# dcdc.net
KiCad netlist of a schematic drawn in Altium Designer
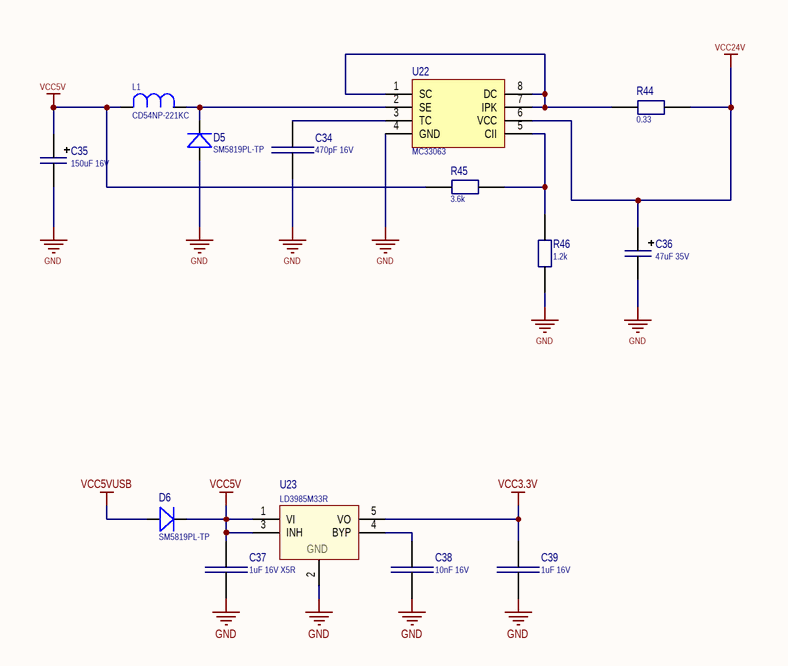
[diagram p0: dcdc.schdoc]

(export (version "E")
  (design (tool "Eeschema 10.0.6"))
  (components
    (comp (ref "C34")
      (value "470pF 16V")
      (footprint "C_0603")
      (description "Capacitor")
      (fields (field (name "PART NUMBER") "CC0603KRX7R9BB471"))
      (libsource (lib "AX_Altium_v2.3") (part "C0603"))
    )
    (comp (ref "C35")
      (value "150uF 16V")
      (footprint "TANTAL_TYPE_D")
      (description "Tantal Capacitor")
      (fields (field (name "PART NUMBER") "T491D157K016AT"))
      (libsource (lib "capacitors") (part "TANTAL_CAP"))
    )
    (comp (ref "C36")
      (value "47uF 35V")
      (footprint "TANTAL_TYPE_X")
      (description "Tantal Capacitor")
      (fields (field (name "PART NUMBER") "T491X476K035AT"))
      (libsource (lib "capacitors") (part "TANTAL_CAP"))
    )
    (comp (ref "C37")
      (value "1uF 16V X5R")
      (footprint "C_0603")
      (description "Capacitor")
      (fields (field (name "PART NUMBER") "CC0603KRX7R7BB105"))
      (libsource (lib "AX_Altium_v2.3") (part "C0603"))
    )
    (comp (ref "C38")
      (value "10nF 16V")
      (footprint "C_0603")
      (description "Capacitor")
      (fields (field (name "PART NUMBER") "CC0603JRX7R7BB103"))
      (libsource (lib "AX_Altium_v2.3") (part "C0603"))
    )
    (comp (ref "C39")
      (value "1uF 16V")
      (footprint "C_0603")
      (description "Capacitor")
      (fields (field (name "PART NUMBER") "CC0603KRX7R7BB105"))
      (libsource (lib "AX_Altium_v2.3") (part "C0603"))
    )
    (comp (ref "D5")
      (value "SM5819PL-TP")
      (footprint "SOD-123")
      (description "Diode")
      (libsource (lib "AX_Altium_v2.3") (part "D_SOD123"))
    )
    (comp (ref "D6")
      (value "SM5819PL-TP")
      (footprint "SOD-123")
      (description "Diode")
      (libsource (lib "AX_Altium_v2.3") (part "D_SOD123"))
    )
    (comp (ref "L1")
      (value "CD54NP-221KC")
      (footprint "CD54NP")
      (description "Inductor")
      (libsource (lib "AX_Altium_v2.3") (part "L_CD54NP"))
    )
    (comp (ref "R44")
      (value "0.33")
      (footprint "R_1206")
      (description "Resistor")
      (fields (field (name "PART NUMBER") "RL1206FR-070R33L"))
      (libsource (lib "resistors") (part "RES_SMD"))
    )
    (comp (ref "R45")
      (value "3.6k")
      (footprint "R_0603")
      (description "Resistor")
      (fields (field (name "PART NUMBER") "RC0603FR-073K6L"))
      (libsource (lib "resistors") (part "RES_SMD"))
    )
    (comp (ref "R46")
      (value "1.2k")
      (footprint "R_0603")
      (description "Resistor")
      (fields (field (name "PART NUMBER") "RC0603FR-071K2L"))
      (libsource (lib "resistors") (part "RES_SMD"))
    )
    (comp (ref "U22")
      (value "MC33063")
      (footprint "SO-8")
      (description "Step-up/down IC")
      (libsource (lib "dcdc_ldo_ref") (part "MC33063"))
    )
    (comp (ref "U23")
      (value "LD3985M33R")
      (footprint "SOT23-5")
      (libsource (lib "AX_Altium_v2.3") (part "LD3985M33R"))
    )
  )
  (nets
    (net (code "1") (name "GND") (class "Default")
      (node (ref "C34") (pin "1") (pinfunction "1_1") (pintype "passive"))
      (node (ref "C35") (pin "2") (pinfunction "2_2") (pintype "passive"))
      (node (ref "C36") (pin "2") (pinfunction "2_2") (pintype "passive"))
      (node (ref "C37") (pin "1") (pinfunction "1_1") (pintype "passive"))
      (node (ref "C38") (pin "1") (pinfunction "1_1") (pintype "passive"))
      (node (ref "C39") (pin "1") (pinfunction "1_1") (pintype "passive"))
      (node (ref "D5") (pin "1") (pinfunction "A_1") (pintype "passive"))
      (node (ref "R46") (pin "1") (pinfunction "1_1") (pintype "passive"))
      (node (ref "U22") (pin "4") (pinfunction "GND_4") (pintype "passive"))
      (node (ref "U23") (pin "2") (pinfunction "GND_2") (pintype "passive"))
    )
    (net (code "2") (name "Net-(D5-K)") (class "Default")
      (node (ref "D5") (pin "2") (pinfunction "K_2") (pintype "passive"))
      (node (ref "L1") (pin "1") (pintype "passive"))
      (node (ref "U22") (pin "2") (pinfunction "SE_2") (pintype "passive"))
    )
    (net (code "3") (name "Net-(U22-CII)") (class "Default")
      (node (ref "R45") (pin "2") (pinfunction "2_2") (pintype "passive"))
      (node (ref "R46") (pin "2") (pinfunction "2_2") (pintype "passive"))
      (node (ref "U22") (pin "5") (pinfunction "CII_5") (pintype "passive"))
    )
    (net (code "4") (name "Net-(U22-DC)") (class "Default")
      (node (ref "R44") (pin "2") (pinfunction "2_2") (pintype "passive"))
      (node (ref "U22") (pin "1") (pinfunction "SC_1") (pintype "passive"))
      (node (ref "U22") (pin "7") (pinfunction "IPK_7") (pintype "passive"))
      (node (ref "U22") (pin "8") (pinfunction "DC_8") (pintype "passive"))
    )
    (net (code "5") (name "Net-(U22-TC)") (class "Default")
      (node (ref "C34") (pin "2") (pinfunction "2_2") (pintype "passive"))
      (node (ref "U22") (pin "3") (pinfunction "TC_3") (pintype "passive"))
    )
    (net (code "6") (name "Net-(U23-BYP)") (class "Default")
      (node (ref "C38") (pin "2") (pinfunction "2_2") (pintype "passive"))
      (node (ref "U23") (pin "4") (pinfunction "BYP_4") (pintype "passive"))
    )
    (net (code "7") (name "VCC3.3V") (class "Default")
      (node (ref "C39") (pin "2") (pinfunction "2_2") (pintype "passive"))
      (node (ref "U23") (pin "5") (pinfunction "VO_5") (pintype "passive"))
    )
    (net (code "8") (name "VCC5V") (class "Default")
      (node (ref "C35") (pin "1") (pinfunction "1_1") (pintype "passive"))
      (node (ref "C37") (pin "2") (pinfunction "2_2") (pintype "passive"))
      (node (ref "D6") (pin "2") (pinfunction "K_2") (pintype "passive"))
      (node (ref "L1") (pin "2") (pintype "passive"))
      (node (ref "R45") (pin "1") (pinfunction "1_1") (pintype "passive"))
      (node (ref "U23") (pin "1") (pinfunction "VI_1") (pintype "passive"))
      (node (ref "U23") (pin "3") (pinfunction "INH_3") (pintype "passive"))
    )
    (net (code "9") (name "VCC5VUSB") (class "Default")
      (node (ref "D6") (pin "1") (pinfunction "A_1") (pintype "passive"))
    )
    (net (code "10") (name "VCC24V") (class "Default")
      (node (ref "C36") (pin "1") (pinfunction "1_1") (pintype "passive"))
      (node (ref "R44") (pin "1") (pinfunction "1_1") (pintype "passive"))
      (node (ref "U22") (pin "6") (pinfunction "VCC_6") (pintype "passive"))
    )
  )
)
